# RaceDAQ_POWER.net
KiCad netlist of a schematic drawn in Altium Designer
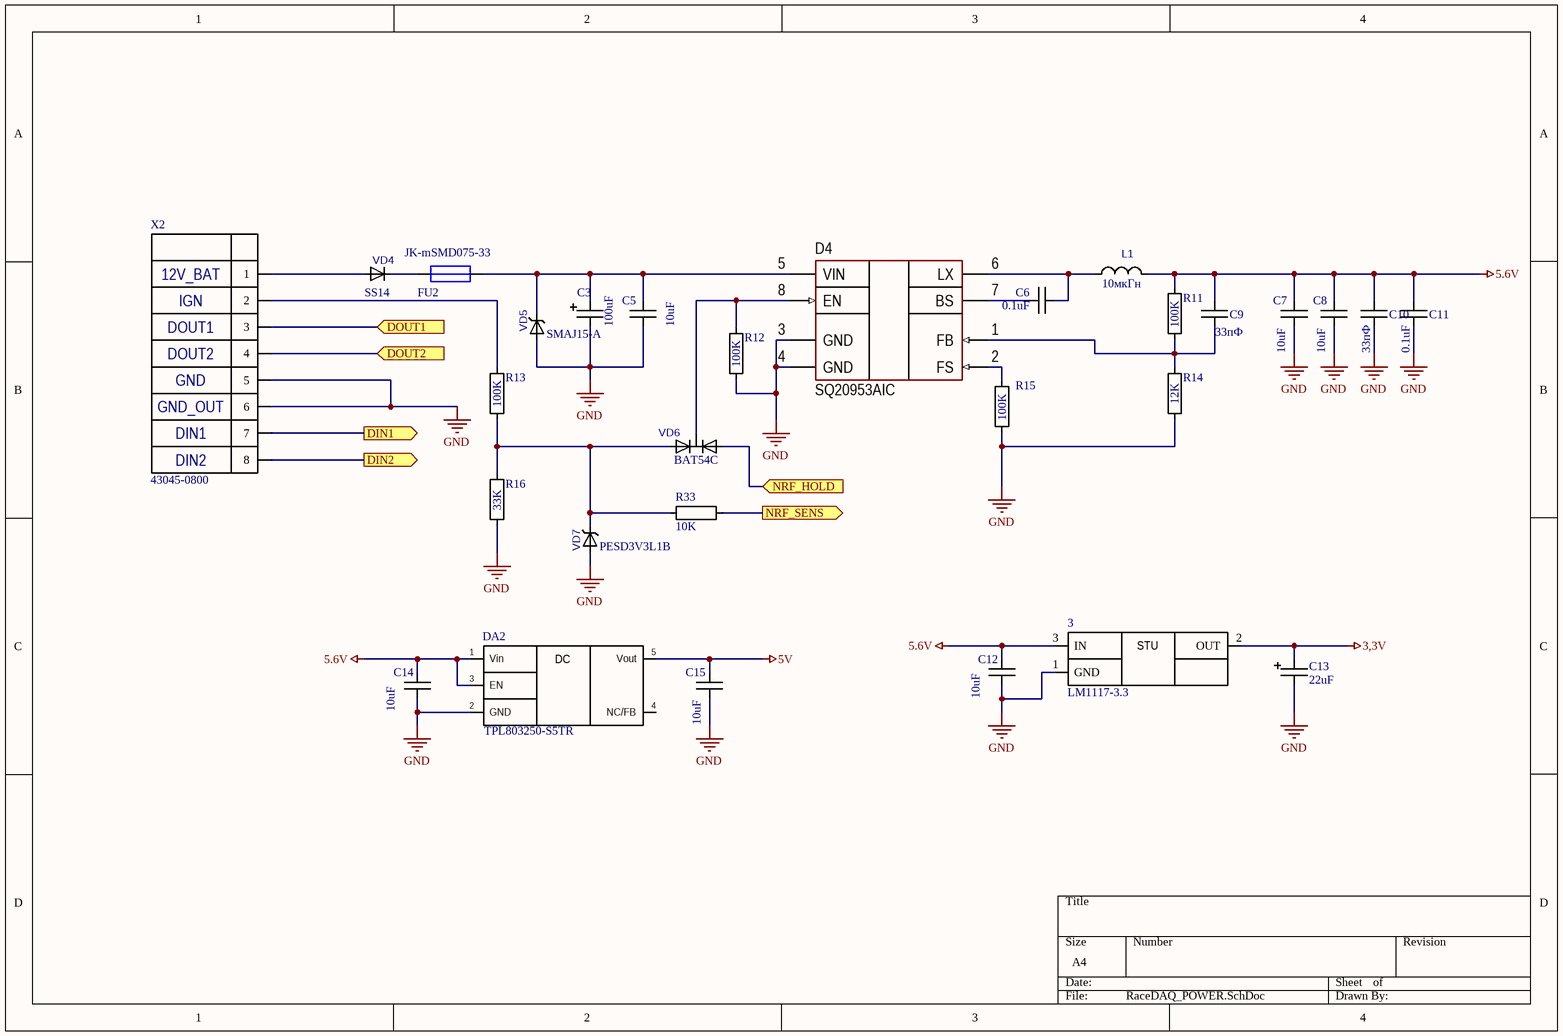
[diagram p0: RaceDAQ_POWER.SchDoc]

(export (version "E")
  (design (tool "Eeschema 10.0.6"))
  (components
    (comp (ref "3")
      (value "LM1117-3.3")
      (footprint "SOT230P700X180-4L40N")
      (libsource (lib "tlib") (part "REF30xx"))
    )
    (comp (ref "C3")
      (value "100uF")
      (footprint "CAPPRD250W50D680H1250")
      (fields (field (name "VOLTAGE") "25V") (field (name "PARTNUMBER") "EEUFR1E101"))
      (libsource (lib "tlib") (part "CPOL"))
    )
    (comp (ref "C5")
      (value "10uF")
      (footprint "CAPC3216X130L50N")
      (fields (field (name "PARTNUMBER") "GRM31CR61E106KA12L") (field (name "VOLTAGE") "25V"))
      (libsource (lib "tlib") (part "CAP"))
    )
    (comp (ref "C6")
      (value "0.1uF")
      (footprint "CAPC1608X90L25N")
      (fields (field (name "VOLTAGE") "50V") (field (name "PARTNUMBER") "CL10B104KB8NNNC"))
      (libsource (lib "tlib") (part "CAP"))
    )
    (comp (ref "C7")
      (value "10uF")
      (footprint "CAPC3216X130L50N")
      (fields (field (name "PARTNUMBER") "GRM31CR61E106KA12L") (field (name "VOLTAGE") "25V"))
      (libsource (lib "tlib") (part "CAP"))
    )
    (comp (ref "C8")
      (value "10uF")
      (footprint "CAPC3216X130L50N")
      (fields (field (name "PARTNUMBER") "GRM31CR61E106KA12L") (field (name "VOLTAGE") "25V"))
      (libsource (lib "tlib") (part "CAP"))
    )
    (comp (ref "C9")
      (value "33пФ")
      (footprint "CAPC1608X90L25N")
      (fields (field (name "VOLTAGE") "50V") (field (name "PARTNUMBER") "CL10C330JB8NNNC,"))
      (libsource (lib "tlib") (part "CAP"))
    )
    (comp (ref "C10")
      (value "33пФ")
      (footprint "CAPC1608X90L25N")
      (fields (field (name "VOLTAGE") "50V") (field (name "PARTNUMBER") "CL10C330JB8NNNC,"))
      (libsource (lib "tlib") (part "CAP"))
    )
    (comp (ref "C11")
      (value "0.1uF")
      (footprint "CAPC1608X90L25N")
      (fields (field (name "VOLTAGE") "50V") (field (name "PARTNUMBER") "CL10B104KB8NNNC"))
      (libsource (lib "tlib") (part "CAP"))
    )
    (comp (ref "C12")
      (value "10uF")
      (footprint "CAPC3216X130L50N")
      (fields (field (name "PARTNUMBER") "GRM31CR61E106KA12L") (field (name "VOLTAGE") "25V"))
      (libsource (lib "tlib") (part "CAP"))
    )
    (comp (ref "C13")
      (value "22uF")
      (footprint "CAPPM3216X180")
      (fields (field (name "PARTNUMBER") "293D226X9010A2TE3"))
      (libsource (lib "tlib") (part "CPOL"))
    )
    (comp (ref "C14")
      (value "10uF")
      (footprint "CAPC3216X130L50N")
      (fields (field (name "PARTNUMBER") "GRM31CR61E106KA12L") (field (name "VOLTAGE") "25V"))
      (libsource (lib "tlib") (part "CAP"))
    )
    (comp (ref "C15")
      (value "10uF")
      (footprint "CAPC3216X130L50N")
      (fields (field (name "PARTNUMBER") "GRM31CR61E106KA12L") (field (name "VOLTAGE") "25V"))
      (libsource (lib "tlib") (part "CAP"))
    )
    (comp (ref "D4")
      (value "~")
      (footprint "8-SOT")
      (description "Buck converter")
      (fields
        (field (name "MANUFACTURER") "Silergy")
        (field (name "VALUEMANUFACTURERPARTNUMBER") "DC/DC buck converter, input 4...60V, 2.1MHz, output 0.765...55V, 0.6A, -40...+125°C, SOT23-8")
        (field (name "PARTNUMBER") "SQ20953AIC")
      )
      (libsource (lib "ic-power-supply") (part "SQ20953AIC"))
    )
    (comp (ref "DA2")
      (value "TPL803250-S5TR")
      (footprint "SOT95P280X145-5L30N")
      (libsource (lib "tlib") (part "TPS763xx"))
    )
    (comp (ref "FU2")
      (value "JK-mSMD075-33")
      (footprint "FUSE: 1812")
      (description "Предохраниетель ток срабатывания 1,5А, ток удержания 750мА")
      (libsource (lib "Fuse") (part "JK-mSMD075-33"))
    )
    (comp (ref "L1")
      (value "10мкГн")
      (footprint "MPH0630")
      (fields (field (name "PARTNUMBER") "MWSA0603S-100MT"))
      (libsource (lib "tlib") (part "COIL"))
    )
    (comp (ref "R11")
      (value "100K")
      (footprint "RESC1608X55L25N")
      (fields (field (name "PARTNUMBER") "RC0603FR-07100KL"))
      (libsource (lib "tlib") (part "RES"))
    )
    (comp (ref "R12")
      (value "100K")
      (footprint "RESC1608X55L25N")
      (fields (field (name "PARTNUMBER") "RC0603FR-07100KL"))
      (libsource (lib "tlib") (part "RES"))
    )
    (comp (ref "R13")
      (value "100K")
      (footprint "RESC1608X55L25N")
      (fields (field (name "PARTNUMBER") "RC0603FR-07100KL"))
      (libsource (lib "tlib") (part "RES"))
    )
    (comp (ref "R14")
      (value "12K")
      (footprint "RESC1608X55L25N")
      (fields (field (name "PARTNUMBER") "RC0603FR-0712KL"))
      (libsource (lib "tlib") (part "RES"))
    )
    (comp (ref "R15")
      (value "100K")
      (footprint "RESC1608X55L25N")
      (fields (field (name "PARTNUMBER") "RC0603FR-07100KL"))
      (libsource (lib "tlib") (part "RES"))
    )
    (comp (ref "R16")
      (value "33K")
      (footprint "RESC1608X55L25N")
      (fields (field (name "PARTNUMBER") "RC0603FR-0733KL"))
      (libsource (lib "tlib") (part "RES"))
    )
    (comp (ref "R33") (value "10K") (footprint "RESC2012X60L35N") (libsource (lib "tlib") (part "RES")))
    (comp (ref "VD4") (value "SS14") (footprint "DIOM5436X247N") (libsource (lib "tlib") (part "DIODE_AC")))
    (comp (ref "VD5") (value "SMAJ15-A") (footprint "DIOM5126X229") (libsource (lib "tlib") (part "TVS_AC")))
    (comp (ref "VD6")
      (value "BAT54C")
      (footprint "SOT95P240X110-3L16")
      (libsource (lib "tlib") (part "BAT54C"))
    )
    (comp (ref "VD7")
      (value "PESD3V3L1B")
      (footprint "SODFL1608X65N")
      (libsource (lib "tlib") (part "TVS_AC"))
    )
    (comp (ref "X2") (value "43045-0800") (footprint "43045-0800") (libsource (lib "tlib") (part "X8")))
  )
  (nets
    (net (code "1") (name "/DIN1") (class "Default")
      (node (ref "X2") (pin "7") (pinfunction "7_7") (pintype "passive"))
    )
    (net (code "2") (name "/DIN2") (class "Default")
      (node (ref "X2") (pin "8") (pinfunction "8_8") (pintype "passive"))
    )
    (net (code "3") (name "/DOUT1") (class "Default")
      (node (ref "X2") (pin "3") (pinfunction "3_3") (pintype "passive"))
    )
    (net (code "4") (name "/DOUT2") (class "Default")
      (node (ref "X2") (pin "4") (pinfunction "4_4") (pintype "passive"))
    )
    (net (code "5") (name "/NRF_HOLD") (class "Default") (node (ref "VD6") (pin "2") (pintype "passive")))
    (net (code "6") (name "/NRF_SENS") (class "Default")
      (node (ref "R33") (pin "1") (pinfunction "1_1") (pintype "passive"))
    )
    (net (code "7") (name "3,3V") (class "Default")
      (node (ref "3") (pin "2") (pinfunction "OUT_2") (pintype "passive"))
      (node (ref "C13") (pin "1") (pintype "passive"))
    )
    (net (code "8") (name "5.6V") (class "Default")
      (node (ref "3") (pin "3") (pinfunction "IN_3") (pintype "passive"))
      (node (ref "C10") (pin "1") (pintype "passive"))
      (node (ref "C11") (pin "1") (pintype "passive"))
      (node (ref "C12") (pin "1") (pintype "passive"))
      (node (ref "C14") (pin "1") (pintype "passive"))
      (node (ref "C7") (pin "1") (pintype "passive"))
      (node (ref "C8") (pin "1") (pintype "passive"))
      (node (ref "C9") (pin "1") (pintype "passive"))
      (node (ref "DA2") (pin "1") (pinfunction "Vin_1") (pintype "passive"))
      (node (ref "DA2") (pin "3") (pinfunction "EN_3") (pintype "passive"))
      (node (ref "L1") (pin "2") (pintype "passive"))
      (node (ref "R11") (pin "1") (pinfunction "1_1") (pintype "passive"))
    )
    (net (code "9") (name "5V") (class "Default")
      (node (ref "C15") (pin "1") (pintype "passive"))
      (node (ref "DA2") (pin "5") (pinfunction "Vout_5") (pintype "passive"))
    )
    (net (code "10") (name "GND") (class "Default")
      (node (ref "3") (pin "1") (pinfunction "GND_1") (pintype "passive"))
      (node (ref "C10") (pin "2") (pintype "passive"))
      (node (ref "C11") (pin "2") (pintype "passive"))
      (node (ref "C12") (pin "2") (pintype "passive"))
      (node (ref "C13") (pin "2") (pintype "passive"))
      (node (ref "C14") (pin "2") (pintype "passive"))
      (node (ref "C15") (pin "2") (pintype "passive"))
      (node (ref "C3") (pin "2") (pintype "passive"))
      (node (ref "C5") (pin "2") (pintype "passive"))
      (node (ref "C7") (pin "2") (pintype "passive"))
      (node (ref "C8") (pin "2") (pintype "passive"))
      (node (ref "D4") (pin "3") (pinfunction "GND_3") (pintype "passive"))
      (node (ref "D4") (pin "4") (pinfunction "GND_4") (pintype "passive"))
      (node (ref "DA2") (pin "2") (pinfunction "GND_2") (pintype "passive"))
      (node (ref "R12") (pin "2") (pinfunction "2_2") (pintype "passive"))
      (node (ref "R14") (pin "2") (pinfunction "2_2") (pintype "passive"))
      (node (ref "R15") (pin "2") (pinfunction "2_2") (pintype "passive"))
      (node (ref "R16") (pin "2") (pinfunction "2_2") (pintype "passive"))
      (node (ref "VD5") (pin "A") (pintype "passive"))
      (node (ref "VD7") (pin "A") (pintype "passive"))
      (node (ref "X2") (pin "5") (pinfunction "5_5") (pintype "passive"))
      (node (ref "X2") (pin "6") (pinfunction "6_6") (pintype "passive"))
    )
    (net (code "11") (name "Net-(D4-BS)") (class "Default")
      (node (ref "C6") (pin "1") (pintype "passive"))
      (node (ref "D4") (pin "7") (pinfunction "BS_7") (pintype "passive"))
    )
    (net (code "12") (name "Net-(D4-EN)") (class "Default")
      (node (ref "D4") (pin "8") (pinfunction "EN_8") (pintype "input"))
      (node (ref "R12") (pin "1") (pinfunction "1_1") (pintype "passive"))
      (node (ref "VD6") (pin "3") (pintype "passive"))
    )
    (net (code "13") (name "Net-(D4-FB)") (class "Default")
      (node (ref "C9") (pin "2") (pintype "passive"))
      (node (ref "D4") (pin "1") (pinfunction "FB_1") (pintype "input"))
      (node (ref "R11") (pin "2") (pinfunction "2_2") (pintype "passive"))
      (node (ref "R14") (pin "1") (pinfunction "1_1") (pintype "passive"))
    )
    (net (code "14") (name "Net-(D4-FS)") (class "Default")
      (node (ref "D4") (pin "2") (pinfunction "FS_2") (pintype "input"))
      (node (ref "R15") (pin "1") (pinfunction "1_1") (pintype "passive"))
    )
    (net (code "15") (name "Net-(D4-LX)") (class "Default")
      (node (ref "C6") (pin "2") (pintype "passive"))
      (node (ref "D4") (pin "6") (pinfunction "LX_6") (pintype "passive"))
      (node (ref "L1") (pin "1") (pintype "passive"))
    )
    (net (code "16") (name "Net-(D4-VIN)") (class "Default")
      (node (ref "C3") (pin "1") (pintype "passive"))
      (node (ref "C5") (pin "1") (pintype "passive"))
      (node (ref "D4") (pin "5") (pinfunction "VIN_5") (pintype "passive"))
      (node (ref "FU2") (pin "2") (pinfunction "2_2") (pintype "passive"))
      (node (ref "VD5") (pin "C") (pintype "passive"))
    )
    (net (code "17") (name "Net-(FU2-Pad1)") (class "Default")
      (node (ref "FU2") (pin "1") (pinfunction "1_1") (pintype "passive"))
      (node (ref "VD4") (pin "C") (pintype "passive"))
    )
    (net (code "18") (name "Net-(R13-Pad1)") (class "Default")
      (node (ref "R13") (pin "1") (pinfunction "1_1") (pintype "passive"))
      (node (ref "X2") (pin "2") (pinfunction "2_2") (pintype "passive"))
    )
    (net (code "19") (name "Net-(R13-Pad2)") (class "Default")
      (node (ref "R13") (pin "2") (pinfunction "2_2") (pintype "passive"))
      (node (ref "R16") (pin "1") (pinfunction "1_1") (pintype "passive"))
      (node (ref "R33") (pin "2") (pinfunction "2_2") (pintype "passive"))
      (node (ref "VD6") (pin "1") (pintype "passive"))
      (node (ref "VD7") (pin "C") (pintype "passive"))
    )
    (net (code "20") (name "Net-(VD4-PadA)") (class "Default")
      (node (ref "VD4") (pin "A") (pintype "passive"))
      (node (ref "X2") (pin "1") (pinfunction "1_1") (pintype "passive"))
    )
    (net (code "21") (name "unconnected-(DA2-NC{slash}FB-Pad4)") (class "Default")
      (node (ref "DA2") (pin "4") (pinfunction "NC/FB_4") (pintype "passive"))
    )
  )
)
